# lpc_serial.net
KiCad netlist of a schematic drawn in EAGLE
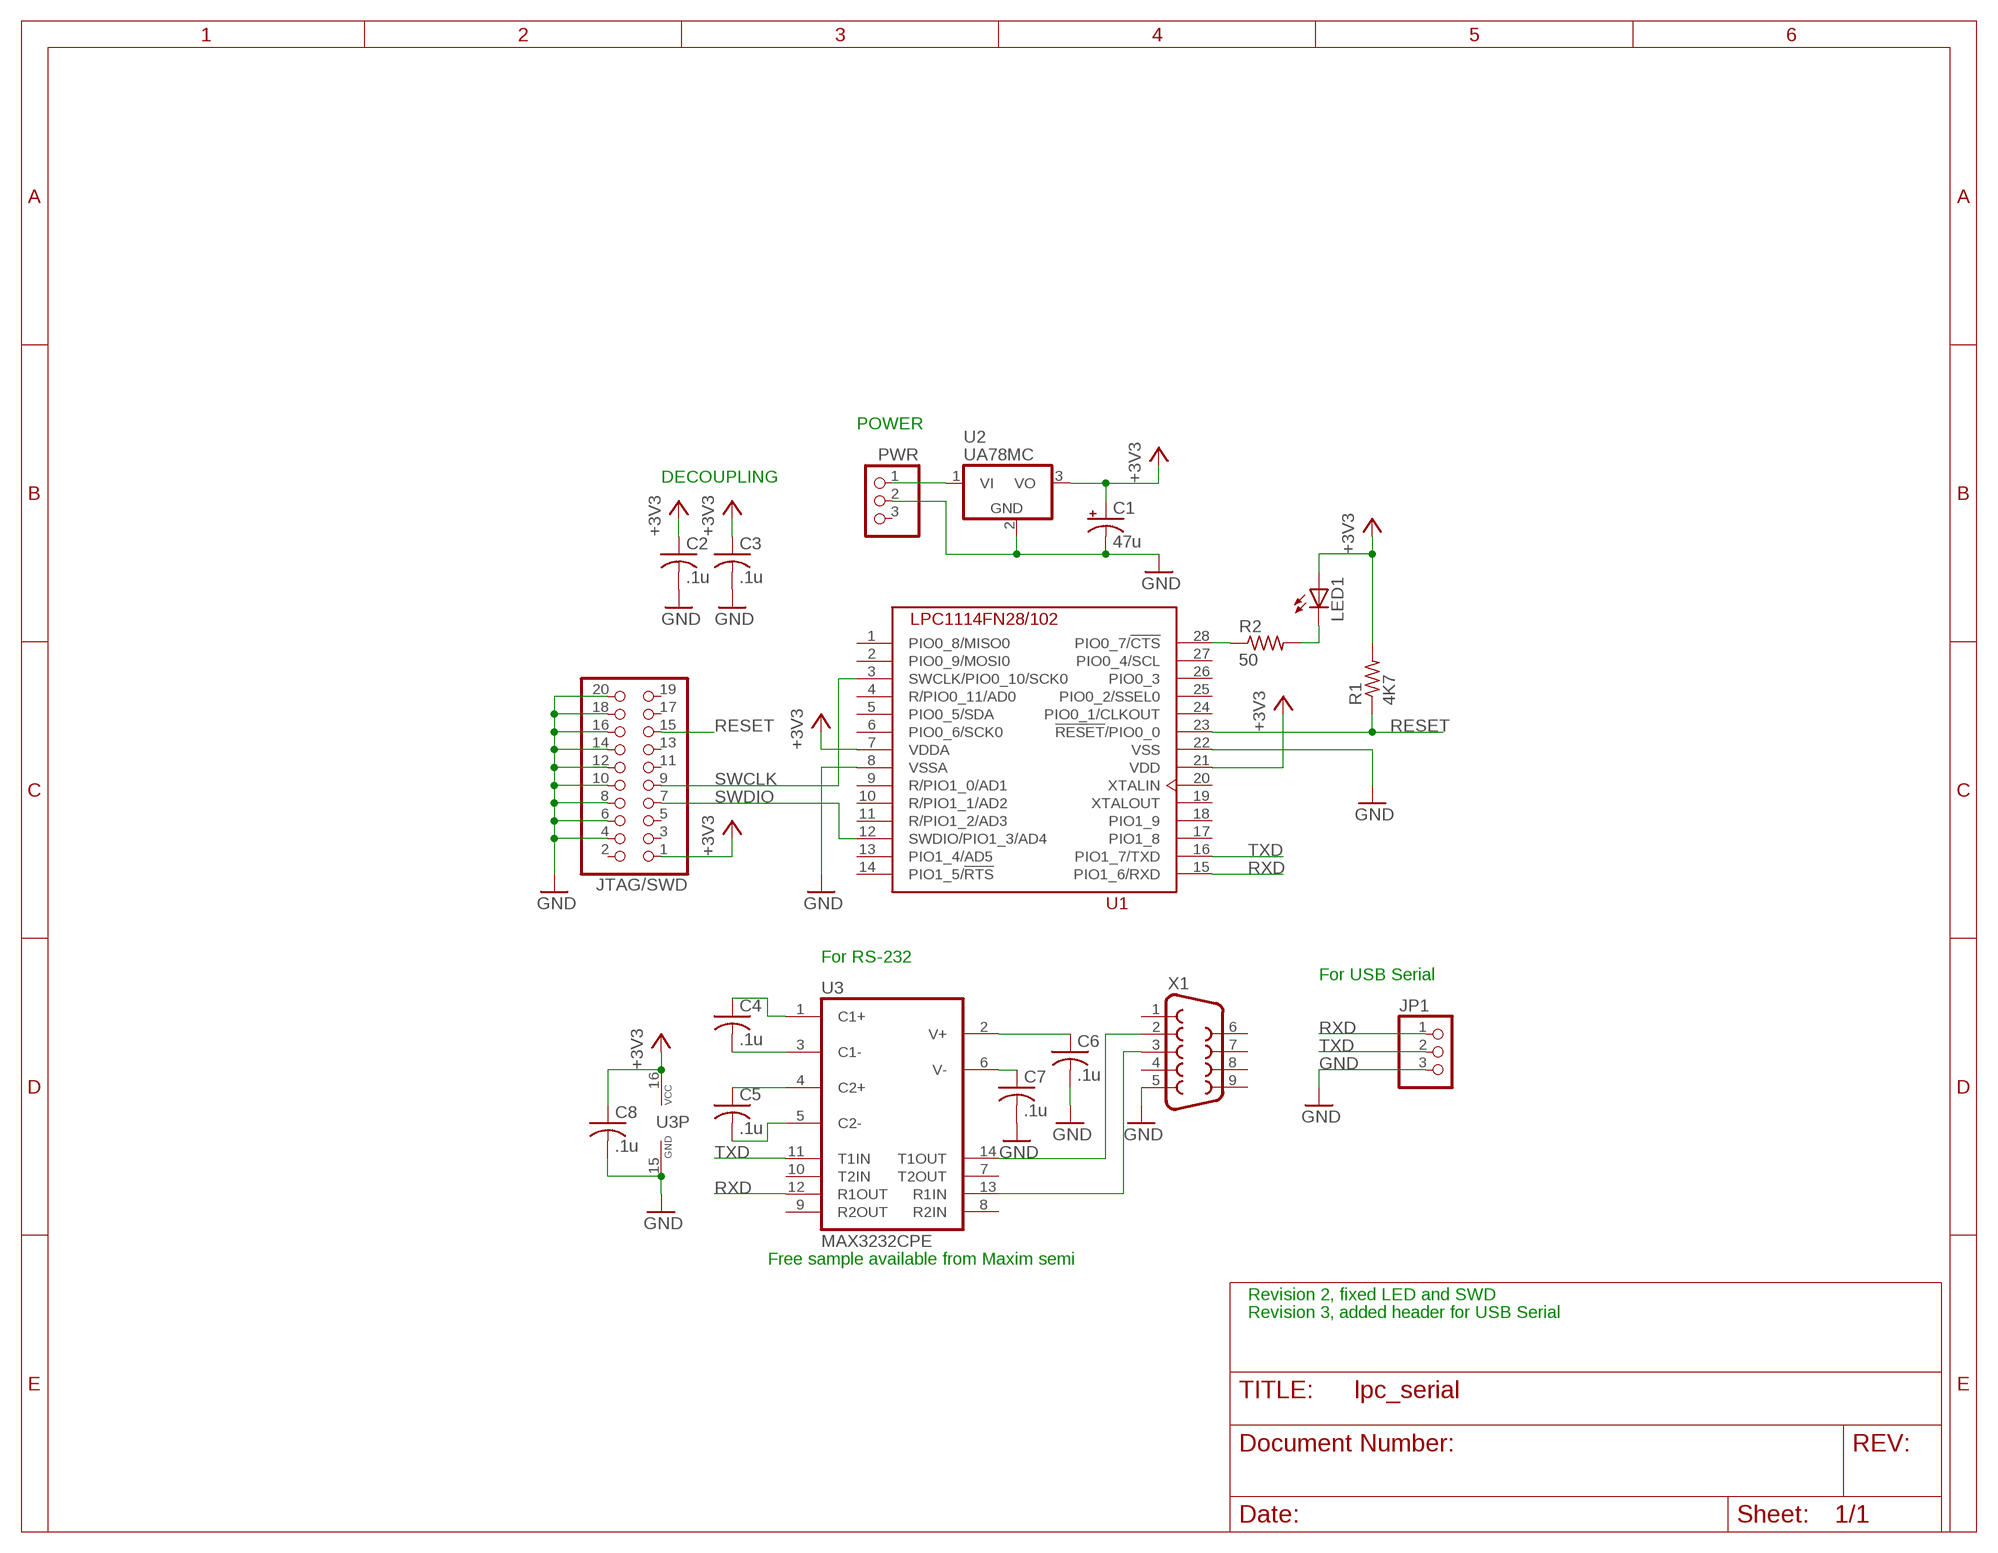
[diagram p0: schematic, sheet 1]

(export (version "E")
  (design (tool "Eeschema 10.0.6"))
  (components
    (comp (ref "C1")
      (value "47u")
      (footprint "eagle-import:E3,5-8")
      (libsource (lib "eagle-import") (part "CPOL-USE3.5-8"))
    )
    (comp (ref "C2")
      (value ".1u")
      (footprint "eagle-import:C050-024X044")
      (libsource (lib "eagle-import") (part "C-US050-024X044"))
    )
    (comp (ref "C3")
      (value ".1u")
      (footprint "eagle-import:C050-024X044")
      (libsource (lib "eagle-import") (part "C-US050-024X044"))
    )
    (comp (ref "C4")
      (value ".1u")
      (footprint "eagle-import:C050-024X044")
      (libsource (lib "eagle-import") (part "C-US050-024X044"))
    )
    (comp (ref "C5")
      (value ".1u")
      (footprint "eagle-import:C050-024X044")
      (libsource (lib "eagle-import") (part "C-US050-024X044"))
    )
    (comp (ref "C6")
      (value ".1u")
      (footprint "eagle-import:C050-024X044")
      (libsource (lib "eagle-import") (part "C-US050-024X044"))
    )
    (comp (ref "C7")
      (value ".1u")
      (footprint "eagle-import:C050-024X044")
      (libsource (lib "eagle-import") (part "C-US050-024X044"))
    )
    (comp (ref "C8")
      (value ".1u")
      (footprint "eagle-import:C050-024X044")
      (libsource (lib "eagle-import") (part "C-US050-024X044"))
    )
    (comp (ref "JP1")
      (value "PINHD-1X3")
      (footprint "eagle-import:1X03")
      (libsource (lib "eagle-import") (part "PINHD-1X3"))
    )
    (comp (ref "JTAG/SWD")
      (value "PINHD-2X10")
      (footprint "eagle-import:2X10")
      (libsource (lib "eagle-import") (part "PINHD-2X10"))
    )
    (comp (ref "LED1")
      (value "LED10MM")
      (footprint "eagle-import:LED10MM")
      (libsource (lib "eagle-import") (part "LED10MM"))
    )
    (comp (ref "PWR")
      (value "PINHD-1X3")
      (footprint "eagle-import:1X03")
      (libsource (lib "eagle-import") (part "PINHD-1X3"))
    )
    (comp (ref "R1")
      (value "4K7")
      (footprint "eagle-import:0207_10")
      (libsource (lib "eagle-import") (part "R-US_0207/10"))
    )
    (comp (ref "R2")
      (value "50")
      (footprint "eagle-import:0207_10")
      (libsource (lib "eagle-import") (part "R-US_0207/10"))
    )
    (comp (ref "U1")
      (value "LPC1114FN28/102")
      (footprint "eagle-import:DIL28-6")
      (libsource (lib "eagle-import") (part "LPC1114FN28/102"))
    )
    (comp (ref "U2")
      (value "UA78MC")
      (footprint "eagle-import:TO220V")
      (libsource (lib "eagle-import") (part "UA78MC"))
    )
    (comp (ref "U3")
      (value "MAX3232CPE")
      (footprint "eagle-import:DIL16")
      (libsource (lib "eagle-import") (part "MAX3232PEC"))
    )
    (comp (ref "X1")
      (value "F09H")
      (footprint "eagle-import:F09H")
      (libsource (lib "eagle-import") (part "F09H"))
    )
  )
  (nets
    (net (code "1") (name "+3V3") (class "Default")
      (node (ref "C1") (pin "+") (pinfunction "+_+") (pintype "passive"))
      (node (ref "C2") (pin "1") (pinfunction "1_1") (pintype "passive"))
      (node (ref "C3") (pin "1") (pinfunction "1_1") (pintype "passive"))
      (node (ref "C8") (pin "1") (pinfunction "1_1") (pintype "passive"))
      (node (ref "JTAG/SWD") (pin "1") (pinfunction "1_1") (pintype "passive"))
      (node (ref "LED1") (pin "A") (pinfunction "A_A") (pintype "passive"))
      (node (ref "R1") (pin "2") (pinfunction "2_2") (pintype "passive"))
      (node (ref "U1") (pin "21") (pinfunction "VDD_21") (pintype "power_in"))
      (node (ref "U1") (pin "7") (pinfunction "VDDA_7") (pintype "power_in"))
      (node (ref "U2") (pin "3") (pinfunction "VO_3") (pintype "passive"))
      (node (ref "U3") (pin "16") (pinfunction "VCC_16") (pintype "power_in"))
    )
    (net (code "2") (name "/RESET") (class "Default")
      (node (ref "JTAG/SWD") (pin "15") (pinfunction "15_15") (pintype "passive"))
      (node (ref "R1") (pin "1") (pinfunction "1_1") (pintype "passive"))
      (node (ref "U1") (pin "23") (pinfunction "~{RESET}/PIO0_0_23") (pintype "bidirectional"))
    )
    (net (code "3") (name "/RXD") (class "Default")
      (node (ref "JP1") (pin "1") (pinfunction "1_1") (pintype "passive"))
      (node (ref "U1") (pin "15") (pinfunction "PIO1_6/RXD_15") (pintype "bidirectional"))
      (node (ref "U3") (pin "12") (pinfunction "R1OUT_12") (pintype "output"))
    )
    (net (code "4") (name "/SWCLK") (class "Default")
      (node (ref "JTAG/SWD") (pin "9") (pinfunction "9_9") (pintype "passive"))
      (node (ref "U1") (pin "3") (pinfunction "SWCLK/PIO0_10/SCK0_3") (pintype "bidirectional"))
    )
    (net (code "5") (name "/SWDIO") (class "Default")
      (node (ref "JTAG/SWD") (pin "7") (pinfunction "7_7") (pintype "passive"))
      (node (ref "U1") (pin "12") (pinfunction "SWDIO/PIO1_3/AD4_12") (pintype "bidirectional"))
    )
    (net (code "6") (name "/TXD") (class "Default")
      (node (ref "JP1") (pin "2") (pinfunction "2_2") (pintype "passive"))
      (node (ref "U1") (pin "16") (pinfunction "PIO1_7/TXD_16") (pintype "bidirectional"))
      (node (ref "U3") (pin "11") (pinfunction "T1IN_11") (pintype "input"))
    )
    (net (code "7") (name "GND") (class "Default")
      (node (ref "C1") (pin "-") (pinfunction "-_-") (pintype "passive"))
      (node (ref "C2") (pin "2") (pinfunction "2_2") (pintype "passive"))
      (node (ref "C3") (pin "2") (pinfunction "2_2") (pintype "passive"))
      (node (ref "C6") (pin "2") (pinfunction "2_2") (pintype "passive"))
      (node (ref "C7") (pin "2") (pinfunction "2_2") (pintype "passive"))
      (node (ref "C8") (pin "2") (pinfunction "2_2") (pintype "passive"))
      (node (ref "JP1") (pin "3") (pinfunction "3_3") (pintype "passive"))
      (node (ref "JTAG/SWD") (pin "10") (pinfunction "10_10") (pintype "passive"))
      (node (ref "JTAG/SWD") (pin "12") (pinfunction "12_12") (pintype "passive"))
      (node (ref "JTAG/SWD") (pin "14") (pinfunction "14_14") (pintype "passive"))
      (node (ref "JTAG/SWD") (pin "16") (pinfunction "16_16") (pintype "passive"))
      (node (ref "JTAG/SWD") (pin "18") (pinfunction "18_18") (pintype "passive"))
      (node (ref "JTAG/SWD") (pin "20") (pinfunction "20_20") (pintype "passive"))
      (node (ref "JTAG/SWD") (pin "4") (pinfunction "4_4") (pintype "passive"))
      (node (ref "JTAG/SWD") (pin "6") (pinfunction "6_6") (pintype "passive"))
      (node (ref "JTAG/SWD") (pin "8") (pinfunction "8_8") (pintype "passive"))
      (node (ref "PWR") (pin "2") (pinfunction "2_2") (pintype "passive"))
      (node (ref "U1") (pin "22") (pinfunction "VSS_22") (pintype "power_in"))
      (node (ref "U1") (pin "8") (pinfunction "VSSA_8") (pintype "power_in"))
      (node (ref "U2") (pin "2") (pinfunction "GND_2") (pintype "passive"))
      (node (ref "U3") (pin "15") (pinfunction "GND_15") (pintype "power_in"))
      (node (ref "X1") (pin "5") (pinfunction "5_5") (pintype "passive"))
    )
    (net (code "8") (name "Net-(LED1-C)") (class "Default")
      (node (ref "LED1") (pin "K") (pinfunction "C_K") (pintype "passive"))
      (node (ref "R2") (pin "2") (pinfunction "2_2") (pintype "passive"))
    )
    (net (code "9") (name "Net-(U1-PIO0_7{slash}~{CTS})") (class "Default")
      (node (ref "R2") (pin "1") (pinfunction "1_1") (pintype "passive"))
      (node (ref "U1") (pin "28") (pinfunction "PIO0_7/~{CTS}_28") (pintype "bidirectional"))
    )
    (net (code "10") (name "Net-(U2-VI)") (class "Default")
      (node (ref "PWR") (pin "1") (pinfunction "1_1") (pintype "passive"))
      (node (ref "U2") (pin "1") (pinfunction "VI_1") (pintype "input"))
    )
    (net (code "11") (name "Net-(U3A-C1+)") (class "Default")
      (node (ref "C4") (pin "1") (pinfunction "1_1") (pintype "passive"))
      (node (ref "U3") (pin "1") (pinfunction "C1+_1") (pintype "bidirectional"))
    )
    (net (code "12") (name "Net-(U3A-C1-)") (class "Default")
      (node (ref "C4") (pin "2") (pinfunction "2_2") (pintype "passive"))
      (node (ref "U3") (pin "3") (pinfunction "C1-_3") (pintype "bidirectional"))
    )
    (net (code "13") (name "Net-(U3A-C2+)") (class "Default")
      (node (ref "C5") (pin "1") (pinfunction "1_1") (pintype "passive"))
      (node (ref "U3") (pin "4") (pinfunction "C2+_4") (pintype "bidirectional"))
    )
    (net (code "14") (name "Net-(U3A-C2-)") (class "Default")
      (node (ref "C5") (pin "2") (pinfunction "2_2") (pintype "passive"))
      (node (ref "U3") (pin "5") (pinfunction "C2-_5") (pintype "bidirectional"))
    )
    (net (code "15") (name "Net-(U3A-R1IN)") (class "Default")
      (node (ref "U3") (pin "13") (pinfunction "R1IN_13") (pintype "input"))
      (node (ref "X1") (pin "3") (pinfunction "3_3") (pintype "passive"))
    )
    (net (code "16") (name "Net-(U3A-T1OUT)") (class "Default")
      (node (ref "U3") (pin "14") (pinfunction "T1OUT_14") (pintype "output"))
      (node (ref "X1") (pin "2") (pinfunction "2_2") (pintype "passive"))
    )
    (net (code "17") (name "Net-(U3A-V+)") (class "Default")
      (node (ref "C6") (pin "1") (pinfunction "1_1") (pintype "passive"))
      (node (ref "U3") (pin "2") (pinfunction "V+_2") (pintype "bidirectional"))
    )
    (net (code "18") (name "Net-(U3A-V-)") (class "Default")
      (node (ref "C7") (pin "1") (pinfunction "1_1") (pintype "passive"))
      (node (ref "U3") (pin "6") (pinfunction "V-_6") (pintype "bidirectional"))
    )
    (net (code "19") (name "unconnected-(JTAG/SWD-Pad2)") (class "Default")
      (node (ref "JTAG/SWD") (pin "2") (pinfunction "2_2") (pintype "passive"))
    )
    (net (code "20") (name "unconnected-(JTAG/SWD-Pad3)") (class "Default")
      (node (ref "JTAG/SWD") (pin "3") (pinfunction "3_3") (pintype "passive"))
    )
    (net (code "21") (name "unconnected-(JTAG/SWD-Pad5)") (class "Default")
      (node (ref "JTAG/SWD") (pin "5") (pinfunction "5_5") (pintype "passive"))
    )
    (net (code "22") (name "unconnected-(JTAG/SWD-Pad11)") (class "Default")
      (node (ref "JTAG/SWD") (pin "11") (pinfunction "11_11") (pintype "passive"))
    )
    (net (code "23") (name "unconnected-(JTAG/SWD-Pad13)") (class "Default")
      (node (ref "JTAG/SWD") (pin "13") (pinfunction "13_13") (pintype "passive"))
    )
    (net (code "24") (name "unconnected-(JTAG/SWD-Pad17)") (class "Default")
      (node (ref "JTAG/SWD") (pin "17") (pinfunction "17_17") (pintype "passive"))
    )
    (net (code "25") (name "unconnected-(JTAG/SWD-Pad19)") (class "Default")
      (node (ref "JTAG/SWD") (pin "19") (pinfunction "19_19") (pintype "passive"))
    )
    (net (code "26") (name "unconnected-(PWR-Pad3)") (class "Default")
      (node (ref "PWR") (pin "3") (pinfunction "3_3") (pintype "passive"))
    )
    (net (code "27") (name "unconnected-(U1-PIO0_1{slash}CLKOUT-Pad24)") (class "Default")
      (node (ref "U1") (pin "24") (pinfunction "PIO0_1/CLKOUT_24") (pintype "bidirectional"))
    )
    (net (code "28") (name "unconnected-(U1-PIO0_2{slash}SSEL0-Pad25)") (class "Default")
      (node (ref "U1") (pin "25") (pinfunction "PIO0_2/SSEL0_25") (pintype "bidirectional"))
    )
    (net (code "29") (name "unconnected-(U1-PIO0_3-Pad26)") (class "Default")
      (node (ref "U1") (pin "26") (pinfunction "PIO0_3_26") (pintype "bidirectional"))
    )
    (net (code "30") (name "unconnected-(U1-PIO0_4{slash}SCL-Pad27)") (class "Default")
      (node (ref "U1") (pin "27") (pinfunction "PIO0_4/SCL_27") (pintype "bidirectional"))
    )
    (net (code "31") (name "unconnected-(U1-PIO0_5{slash}SDA-Pad5)") (class "Default")
      (node (ref "U1") (pin "5") (pinfunction "PIO0_5/SDA_5") (pintype "bidirectional"))
    )
    (net (code "32") (name "unconnected-(U1-PIO0_6{slash}SCK0-Pad6)") (class "Default")
      (node (ref "U1") (pin "6") (pinfunction "PIO0_6/SCK0_6") (pintype "bidirectional"))
    )
    (net (code "33") (name "unconnected-(U1-PIO0_8{slash}MISO0-Pad1)") (class "Default")
      (node (ref "U1") (pin "1") (pinfunction "PIO0_8/MISO0_1") (pintype "bidirectional"))
    )
    (net (code "34") (name "unconnected-(U1-PIO0_9{slash}MOSI0-Pad2)") (class "Default")
      (node (ref "U1") (pin "2") (pinfunction "PIO0_9/MOSI0_2") (pintype "bidirectional"))
    )
    (net (code "35") (name "unconnected-(U1-PIO1_4{slash}AD5-Pad13)") (class "Default")
      (node (ref "U1") (pin "13") (pinfunction "PIO1_4/AD5_13") (pintype "bidirectional"))
    )
    (net (code "36") (name "unconnected-(U1-PIO1_5{slash}~{RTS}-Pad14)") (class "Default")
      (node (ref "U1") (pin "14") (pinfunction "PIO1_5/~{RTS}_14") (pintype "bidirectional"))
    )
    (net (code "37") (name "unconnected-(U1-PIO1_8-Pad17)") (class "Default")
      (node (ref "U1") (pin "17") (pinfunction "PIO1_8_17") (pintype "bidirectional"))
    )
    (net (code "38") (name "unconnected-(U1-PIO1_9-Pad18)") (class "Default")
      (node (ref "U1") (pin "18") (pinfunction "PIO1_9_18") (pintype "bidirectional"))
    )
    (net (code "39") (name "unconnected-(U1-R{slash}PIO0_11{slash}AD0-Pad4)") (class "Default")
      (node (ref "U1") (pin "4") (pinfunction "R/PIO0_11/AD0_4") (pintype "bidirectional"))
    )
    (net (code "40") (name "unconnected-(U1-R{slash}PIO1_0{slash}AD1-Pad9)") (class "Default")
      (node (ref "U1") (pin "9") (pinfunction "R/PIO1_0/AD1_9") (pintype "bidirectional"))
    )
    (net (code "41") (name "unconnected-(U1-R{slash}PIO1_1{slash}AD2-Pad10)") (class "Default")
      (node (ref "U1") (pin "10") (pinfunction "R/PIO1_1/AD2_10") (pintype "bidirectional"))
    )
    (net (code "42") (name "unconnected-(U1-R{slash}PIO1_2{slash}AD3-Pad11)") (class "Default")
      (node (ref "U1") (pin "11") (pinfunction "R/PIO1_2/AD3_11") (pintype "bidirectional"))
    )
    (net (code "43") (name "unconnected-(U1-XTALIN-Pad20)") (class "Default")
      (node (ref "U1") (pin "20") (pinfunction "XTALIN_20") (pintype "bidirectional"))
    )
    (net (code "44") (name "unconnected-(U1-XTALOUT-Pad19)") (class "Default")
      (node (ref "U1") (pin "19") (pinfunction "XTALOUT_19") (pintype "output"))
    )
    (net (code "45") (name "unconnected-(U3A-R2IN-Pad8)") (class "Default")
      (node (ref "U3") (pin "8") (pinfunction "R2IN_8") (pintype "input"))
    )
    (net (code "46") (name "unconnected-(U3A-R2OUT-Pad9)") (class "Default")
      (node (ref "U3") (pin "9") (pinfunction "R2OUT_9") (pintype "output"))
    )
    (net (code "47") (name "unconnected-(U3A-T2IN-Pad10)") (class "Default")
      (node (ref "U3") (pin "10") (pinfunction "T2IN_10") (pintype "input"))
    )
    (net (code "48") (name "unconnected-(U3A-T2OUT-Pad7)") (class "Default")
      (node (ref "U3") (pin "7") (pinfunction "T2OUT_7") (pintype "output"))
    )
    (net (code "49") (name "unconnected-(X1-Pad1)") (class "Default")
      (node (ref "X1") (pin "1") (pinfunction "1_1") (pintype "passive"))
    )
    (net (code "50") (name "unconnected-(X1-Pad4)") (class "Default")
      (node (ref "X1") (pin "4") (pinfunction "4_4") (pintype "passive"))
    )
    (net (code "51") (name "unconnected-(X1-Pad6)") (class "Default")
      (node (ref "X1") (pin "6") (pinfunction "6_6") (pintype "passive"))
    )
    (net (code "52") (name "unconnected-(X1-Pad7)") (class "Default")
      (node (ref "X1") (pin "7") (pinfunction "7_7") (pintype "passive"))
    )
    (net (code "53") (name "unconnected-(X1-Pad8)") (class "Default")
      (node (ref "X1") (pin "8") (pinfunction "8_8") (pintype "passive"))
    )
    (net (code "54") (name "unconnected-(X1-Pad9)") (class "Default")
      (node (ref "X1") (pin "9") (pinfunction "9_9") (pintype "passive"))
    )
  )
)
